# Mouse_Send_SCH.net
KiCad netlist of a schematic drawn in Altium Designer
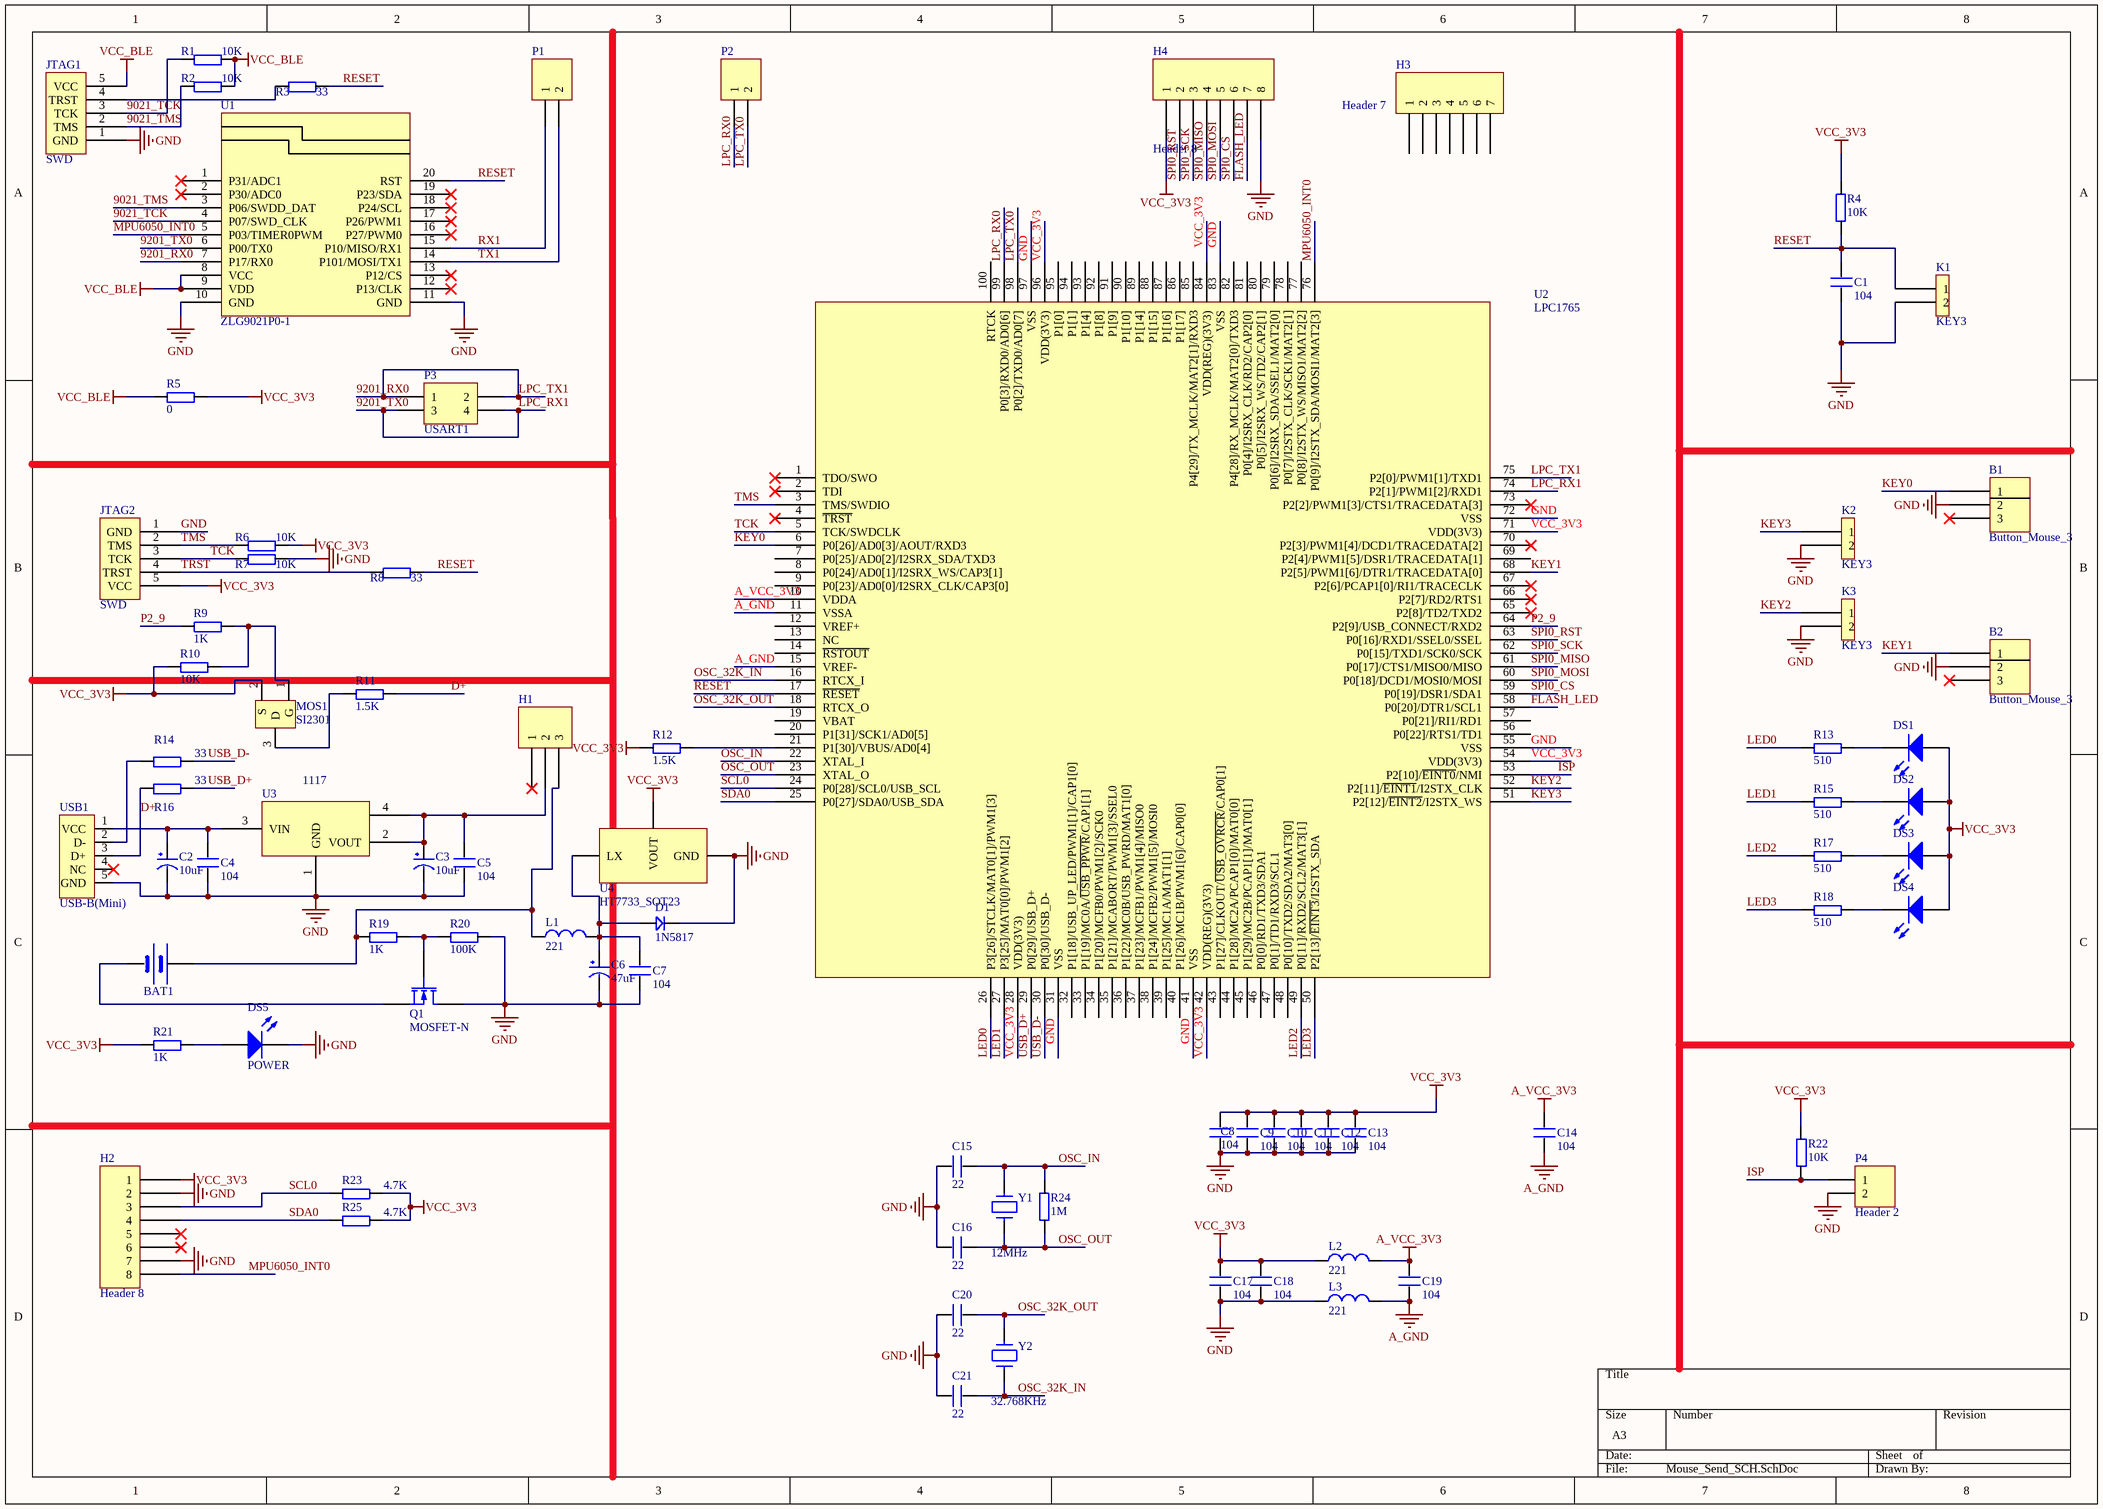
[diagram p0: Mouse_Send_SCH.SchDoc]

(export (version "E")
  (design (tool "Eeschema 10.0.6"))
  (components
    (comp (ref "B1")
      (value "Button_Mouse_3")
      (footprint "Button_Mouse_3")
      (libsource (lib "MY_SCH_Lib") (part "Button_Mouse_3"))
    )
    (comp (ref "B2")
      (value "Button_Mouse_3")
      (footprint "Button_Mouse_3")
      (libsource (lib "MY_SCH_Lib") (part "Button_Mouse_3"))
    )
    (comp (ref "BAT1") (value "BATT") (footprint "BAT_NUM5_2") (libsource (lib "MY_SCH_Lib") (part "BAT")))
    (comp (ref "C1") (value "104") (footprint "0603P") (libsource (lib "MY_SCH_Lib") (part "C")))
    (comp (ref "C2") (value "10uF") (footprint "TAJ_A") (libsource (lib "MY_SCH_Lib") (part "CAP")))
    (comp (ref "C3") (value "10uF") (footprint "TAJ_A") (libsource (lib "MY_SCH_Lib") (part "CAP")))
    (comp (ref "C4") (value "104") (footprint "0603P") (libsource (lib "MY_SCH_Lib") (part "C")))
    (comp (ref "C5") (value "104") (footprint "0603P") (libsource (lib "MY_SCH_Lib") (part "C")))
    (comp (ref "C6") (value "47uF") (footprint "TAJ_A") (libsource (lib "MY_SCH_Lib") (part "CAP")))
    (comp (ref "C7") (value "104") (footprint "0603P") (libsource (lib "MY_SCH_Lib") (part "C")))
    (comp (ref "C8") (value "104") (footprint "0603P") (libsource (lib "MY_SCH_Lib") (part "C")))
    (comp (ref "C9") (value "104") (footprint "0603P") (libsource (lib "MY_SCH_Lib") (part "C")))
    (comp (ref "C10") (value "104") (footprint "0603P") (libsource (lib "MY_SCH_Lib") (part "C")))
    (comp (ref "C11") (value "104") (footprint "0603P") (libsource (lib "MY_SCH_Lib") (part "C")))
    (comp (ref "C12") (value "104") (footprint "0603P") (libsource (lib "MY_SCH_Lib") (part "C")))
    (comp (ref "C13") (value "104") (footprint "0603P") (libsource (lib "MY_SCH_Lib") (part "C")))
    (comp (ref "C14") (value "104") (footprint "0603P") (libsource (lib "MY_SCH_Lib") (part "C")))
    (comp (ref "C15") (value "22") (footprint "0603P") (libsource (lib "MY_SCH_Lib") (part "C")))
    (comp (ref "C16") (value "22") (footprint "0603P") (libsource (lib "MY_SCH_Lib") (part "C")))
    (comp (ref "C17") (value "104") (footprint "0603P") (libsource (lib "MY_SCH_Lib") (part "C")))
    (comp (ref "C18") (value "104") (footprint "0603P") (libsource (lib "MY_SCH_Lib") (part "C")))
    (comp (ref "C19") (value "104") (footprint "0603P") (libsource (lib "MY_SCH_Lib") (part "C")))
    (comp (ref "C20") (value "22") (footprint "0603P") (libsource (lib "MY_SCH_Lib") (part "C")))
    (comp (ref "C21") (value "22") (footprint "0603P") (libsource (lib "MY_SCH_Lib") (part "C")))
    (comp (ref "D1") (value "1N5817") (footprint "DIODE_SOP") (libsource (lib "MY_SCH_Lib") (part "D")))
    (comp (ref "DS1")
      (value "~")
      (footprint "SMDLED")
      (description "Typical RED, GREEN, YELLOW, AMBER GaAs LED")
      (fields (field (name "PUBLISHER") "Altium Limited"))
      (libsource (lib "MY_SCH_Lib") (part "LED2"))
    )
    (comp (ref "DS2")
      (value "~")
      (footprint "SMDLED")
      (description "Typical RED, GREEN, YELLOW, AMBER GaAs LED")
      (fields (field (name "PUBLISHER") "Altium Limited"))
      (libsource (lib "MY_SCH_Lib") (part "LED2"))
    )
    (comp (ref "DS3")
      (value "~")
      (footprint "SMDLED")
      (description "Typical RED, GREEN, YELLOW, AMBER GaAs LED")
      (fields (field (name "PUBLISHER") "Altium Limited"))
      (libsource (lib "MY_SCH_Lib") (part "LED2"))
    )
    (comp (ref "DS4")
      (value "~")
      (footprint "SMDLED")
      (description "Typical RED, GREEN, YELLOW, AMBER GaAs LED")
      (fields (field (name "PUBLISHER") "Altium Limited"))
      (libsource (lib "MY_SCH_Lib") (part "LED2"))
    )
    (comp (ref "DS5")
      (value "POWER")
      (footprint "SMDLED")
      (description "Typical RED, GREEN, YELLOW, AMBER GaAs LED")
      (fields (field (name "PUBLISHER") "Altium Limited"))
      (libsource (lib "MY_SCH_Lib") (part "LED2"))
    )
    (comp (ref "H1") (value "~") (footprint "KEY_B") (libsource (lib "MY_SCH_Lib") (part "Header 3")))
    (comp (ref "H2")
      (value "Header 8")
      (footprint "Header 8")
      (libsource (lib "MY_SCH_Lib") (part "Header 8"))
    )
    (comp (ref "H3") (value "Header 7") (footprint "Head7") (libsource (lib "MY_SCH_Lib") (part "Header 7")))
    (comp (ref "H4") (value "Header 8") (footprint "Header 8") (libsource (lib "") (part "Header 8_1")))
    (comp (ref "JTAG1") (value "SWD") (footprint "HEAD5") (libsource (lib "") (part "SWD_1")))
    (comp (ref "JTAG2") (value "SWD") (footprint "HEAD5") (libsource (lib "MY_SCH_Lib") (part "SWD")))
    (comp (ref "K1") (value "KEY3") (footprint "KEY2") (libsource (lib "MY_SCH_Lib") (part "KEY3")))
    (comp (ref "K2") (value "KEY3") (footprint "KEY2") (libsource (lib "MY_SCH_Lib") (part "KEY3")))
    (comp (ref "K3") (value "KEY3") (footprint "KEY2") (libsource (lib "MY_SCH_Lib") (part "KEY3")))
    (comp (ref "L1") (value "221") (footprint "0603P") (libsource (lib "MY_SCH_Lib") (part "Inductor")))
    (comp (ref "L2") (value "221") (footprint "0603P") (libsource (lib "MY_SCH_Lib") (part "Inductor")))
    (comp (ref "L3") (value "221") (footprint "0603P") (libsource (lib "MY_SCH_Lib") (part "Inductor")))
    (comp (ref "MOS1")
      (value "SI2301")
      (footprint "SOT-23")
      (description "IRLML6401/SI2301")
      (libsource (lib "MY_SCH_Lib") (part "MOS-P"))
    )
    (comp (ref "P1")
      (value "~")
      (footprint "HDR1X2")
      (fields (field (name "PUBLISHER") "Altium Limited"))
      (libsource (lib "") (part "Header 2_1"))
    )
    (comp (ref "P2")
      (value "~")
      (footprint "HDR1X2")
      (fields (field (name "PUBLISHER") "Altium Limited"))
      (libsource (lib "") (part "Header 2_1"))
    )
    (comp (ref "P3")
      (value "USART1")
      (footprint "HDR2X2")
      (description "Header, 2-Pin, Dual row")
      (fields (field (name "PUBLISHER") "Altium Limited"))
      (libsource (lib "MY_SCH_Lib") (part "Header 2X2"))
    )
    (comp (ref "P4")
      (value "Header 2")
      (footprint "HDR1X2")
      (fields (field (name "PUBLISHER") "Altium Limited"))
      (libsource (lib "MY_SCH_Lib") (part "Header 2"))
    )
    (comp (ref "Q1")
      (value "MOSFET-N")
      (footprint "MOSFET_SOT23")
      (description "N-Channel MOSFET")
      (fields (field (name "PUBLISHER") "Altium Limited"))
      (libsource (lib "Miscellaneous Devices") (part "MOSFET-N"))
    )
    (comp (ref "R1") (value "10K") (footprint "0603P") (libsource (lib "MY_SCH_Lib") (part "R")))
    (comp (ref "R2") (value "10K") (footprint "0603P") (libsource (lib "MY_SCH_Lib") (part "R")))
    (comp (ref "R3") (value "33") (footprint "0603P") (libsource (lib "MY_SCH_Lib") (part "R")))
    (comp (ref "R4") (value "10K") (footprint "0603P") (libsource (lib "MY_SCH_Lib") (part "R")))
    (comp (ref "R5") (value "0") (footprint "0603P") (libsource (lib "MY_SCH_Lib") (part "R")))
    (comp (ref "R6") (value "10K") (footprint "0603P") (libsource (lib "MY_SCH_Lib") (part "R")))
    (comp (ref "R7") (value "10K") (footprint "0603P") (libsource (lib "MY_SCH_Lib") (part "R")))
    (comp (ref "R8") (value "33") (footprint "0603P") (libsource (lib "MY_SCH_Lib") (part "R")))
    (comp (ref "R9") (value "1K") (footprint "0603P") (libsource (lib "MY_SCH_Lib") (part "R")))
    (comp (ref "R10") (value "10K") (footprint "0603P") (libsource (lib "MY_SCH_Lib") (part "R")))
    (comp (ref "R11") (value "1.5K") (footprint "0603P") (libsource (lib "MY_SCH_Lib") (part "R")))
    (comp (ref "R12") (value "1.5K") (footprint "0603P") (libsource (lib "MY_SCH_Lib") (part "R")))
    (comp (ref "R13") (value "510") (footprint "0603P") (libsource (lib "MY_SCH_Lib") (part "R")))
    (comp (ref "R14") (value "33") (footprint "0603P") (libsource (lib "MY_SCH_Lib") (part "R")))
    (comp (ref "R15") (value "510") (footprint "0603P") (libsource (lib "MY_SCH_Lib") (part "R")))
    (comp (ref "R16") (value "33") (footprint "0603P") (libsource (lib "MY_SCH_Lib") (part "R")))
    (comp (ref "R17") (value "510") (footprint "0603P") (libsource (lib "MY_SCH_Lib") (part "R")))
    (comp (ref "R18") (value "510") (footprint "0603P") (libsource (lib "MY_SCH_Lib") (part "R")))
    (comp (ref "R19") (value "1K") (footprint "0603P") (libsource (lib "MY_SCH_Lib") (part "R")))
    (comp (ref "R20") (value "100K") (footprint "0603P") (libsource (lib "MY_SCH_Lib") (part "R")))
    (comp (ref "R21") (value "1K") (footprint "0603P") (libsource (lib "MY_SCH_Lib") (part "R")))
    (comp (ref "R22") (value "10K") (footprint "0603P") (libsource (lib "MY_SCH_Lib") (part "R")))
    (comp (ref "R23") (value "4.7K") (footprint "0603P") (libsource (lib "MY_SCH_Lib") (part "R")))
    (comp (ref "R24") (value "1M") (footprint "0603P") (libsource (lib "MY_SCH_Lib") (part "R")))
    (comp (ref "R25") (value "4.7K") (footprint "0603P") (libsource (lib "MY_SCH_Lib") (part "R")))
    (comp (ref "U1")
      (value "ZLG9021P0-1")
      (footprint "ZLG9021P0-1")
      (libsource (lib "MY_SCH_Lib") (part "ZLG9021P0-1"))
    )
    (comp (ref "U2")
      (value "LPC1765")
      (footprint "TQFP-100")
      (libsource (lib "LPC17xx_System_Sch_AD") (part "LPC1765"))
    )
    (comp (ref "U3") (value "1117") (footprint "AMS1117") (libsource (lib "MY_SCH_Lib") (part "1117")))
    (comp (ref "U4")
      (value "HT7733_SOT23")
      (footprint "SOT-23")
      (libsource (lib "LPC17xx_System_Sch_AD") (part "HT7733_SOT23"))
    )
    (comp (ref "USB1")
      (value "USB-B(Mini)")
      (footprint "USB/SM0.8-6H5")
      (libsource (lib "MY_SCH_Lib") (part "USB5"))
    )
    (comp (ref "Y1")
      (value "12MHz")
      (footprint "XTAL_US")
      (description "Crystal")
      (libsource (lib "LPC17xx_System_Sch_AD") (part "CRYSTAL"))
    )
    (comp (ref "Y2")
      (value "32.768KHz")
      (footprint "CRY-32")
      (description "Crystal")
      (libsource (lib "LPC17xx_System_Sch_AD") (part "CRYSTAL"))
    )
  )
  (nets
    (net (code "1") (name "/9021_TCK") (class "Default")
      (node (ref "JTAG1") (pin "3") (pinfunction "TCK_3") (pintype "passive"))
      (node (ref "R1") (pin "1") (pintype "passive"))
      (node (ref "U1") (pin "4") (pinfunction "P07/SWD_CLK_4") (pintype "passive"))
    )
    (net (code "2") (name "/9021_TMS") (class "Default")
      (node (ref "JTAG1") (pin "2") (pinfunction "TMS_2") (pintype "passive"))
      (node (ref "R2") (pin "1") (pintype "passive"))
      (node (ref "U1") (pin "3") (pinfunction "P06/SWDD_DAT_3") (pintype "passive"))
    )
    (net (code "3") (name "/9201_RX0") (class "Default")
      (node (ref "P3") (pin "1") (pinfunction "1_1") (pintype "passive"))
      (node (ref "P3") (pin "2") (pinfunction "2_2") (pintype "passive"))
      (node (ref "U1") (pin "7") (pinfunction "P17/RX0_7") (pintype "passive"))
      (node (ref "U2") (pin "75") (pinfunction "P2[0]/PWM1[1]/TXD1_75") (pintype "passive"))
    )
    (net (code "4") (name "/9201_TX0") (class "Default")
      (node (ref "P3") (pin "3") (pinfunction "3_3") (pintype "passive"))
      (node (ref "P3") (pin "4") (pinfunction "4_4") (pintype "passive"))
      (node (ref "U1") (pin "6") (pinfunction "P00/TX0_6") (pintype "passive"))
      (node (ref "U2") (pin "74") (pinfunction "P2[1]/PWM1[2]/RXD1_74") (pintype "passive"))
    )
    (net (code "5") (name "/D+") (class "Default")
      (node (ref "R11") (pin "2") (pintype "passive"))
      (node (ref "R16") (pin "1") (pintype "passive"))
      (node (ref "USB1") (pin "3") (pinfunction "D+_3") (pintype "passive"))
    )
    (net (code "6") (name "/FLASH_LED") (class "Default")
      (node (ref "H4") (pin "7") (pinfunction "7_7") (pintype "passive"))
      (node (ref "U2") (pin "58") (pinfunction "P0[20]/DTR1/SCL1_58") (pintype "passive"))
    )
    (net (code "7") (name "/ISP") (class "Default")
      (node (ref "P4") (pin "1") (pinfunction "1_1") (pintype "passive"))
      (node (ref "R22") (pin "1") (pintype "passive"))
      (node (ref "U2") (pin "53") (pinfunction "P2[10]/~{EINT0}/NMI_53") (pintype "passive"))
    )
    (net (code "8") (name "/KEY0") (class "Default")
      (node (ref "B1") (pin "1") (pinfunction "1_1") (pintype "passive"))
      (node (ref "U2") (pin "6") (pinfunction "P0[26]/AD0[3]/AOUT/RXD3_6") (pintype "passive"))
    )
    (net (code "9") (name "/KEY1") (class "Default")
      (node (ref "B2") (pin "1") (pinfunction "1_1") (pintype "passive"))
      (node (ref "U2") (pin "68") (pinfunction "P2[5]/PWM1[6]/DTR1/TRACEDATA[0]_68") (pintype "passive"))
    )
    (net (code "10") (name "/KEY2") (class "Default")
      (node (ref "K3") (pin "1") (pinfunction "1_1") (pintype "passive"))
      (node (ref "U2") (pin "52") (pinfunction "P2[11]/~{EINT1}/I2STX_CLK_52") (pintype "passive"))
    )
    (net (code "11") (name "/KEY3") (class "Default")
      (node (ref "K2") (pin "1") (pinfunction "1_1") (pintype "passive"))
      (node (ref "U2") (pin "51") (pinfunction "P2[12]/~{EINT2}/I2STX_WS_51") (pintype "passive"))
    )
    (net (code "12") (name "/LED0") (class "Default")
      (node (ref "R13") (pin "1") (pintype "passive"))
      (node (ref "U2") (pin "26") (pinfunction "P3[26]/STCLK/MAT0[1]/PWM1[3]_26") (pintype "passive"))
    )
    (net (code "13") (name "/LED1") (class "Default")
      (node (ref "R15") (pin "1") (pintype "passive"))
      (node (ref "U2") (pin "27") (pinfunction "P3[25]/MAT0[0]/PWM1[2]_27") (pintype "passive"))
    )
    (net (code "14") (name "/LED2") (class "Default")
      (node (ref "R17") (pin "1") (pintype "passive"))
      (node (ref "U2") (pin "49") (pinfunction "P0[11]/RXD2/SCL2/MAT3[1]_49") (pintype "passive"))
    )
    (net (code "15") (name "/LED3") (class "Default")
      (node (ref "R18") (pin "1") (pintype "passive"))
      (node (ref "U2") (pin "50") (pinfunction "P2[13]/~{EINT3}/I2STX_SDA_50") (pintype "passive"))
    )
    (net (code "16") (name "/LPC_RX0") (class "Default")
      (node (ref "P2") (pin "1") (pinfunction "1_1") (pintype "passive"))
      (node (ref "U2") (pin "99") (pinfunction "P0[3]/RXD0/AD0[6]_99") (pintype "passive"))
    )
    (net (code "17") (name "/LPC_TX0") (class "Default")
      (node (ref "P2") (pin "2") (pinfunction "2_2") (pintype "passive"))
      (node (ref "U2") (pin "98") (pinfunction "P0[2]/TXD0/AD0[7]_98") (pintype "passive"))
    )
    (net (code "18") (name "/MPU6050_INT0") (class "Default")
      (node (ref "H2") (pin "8") (pinfunction "8_8") (pintype "passive"))
      (node (ref "U1") (pin "5") (pinfunction "P03/TIMER0PWM_5") (pintype "passive"))
      (node (ref "U2") (pin "76") (pinfunction "P0[9]/I2STX_SDA/MOSI1/MAT2[3]_76") (pintype "passive"))
    )
    (net (code "19") (name "/OSC_32K_IN") (class "Default")
      (node (ref "C21") (pin "2") (pintype "passive"))
      (node (ref "U2") (pin "16") (pinfunction "RTCX_I_16") (pintype "passive"))
      (node (ref "Y2") (pin "1") (pinfunction "1_1") (pintype "passive"))
    )
    (net (code "20") (name "/OSC_32K_OUT") (class "Default")
      (node (ref "C20") (pin "2") (pintype "passive"))
      (node (ref "U2") (pin "18") (pinfunction "RTCX_O_18") (pintype "passive"))
      (node (ref "Y2") (pin "2") (pinfunction "2_2") (pintype "passive"))
    )
    (net (code "21") (name "/OSC_IN") (class "Default")
      (node (ref "C15") (pin "2") (pintype "passive"))
      (node (ref "R24") (pin "1") (pintype "passive"))
      (node (ref "U2") (pin "22") (pinfunction "XTAL_I_22") (pintype "passive"))
      (node (ref "Y1") (pin "2") (pinfunction "2_2") (pintype "passive"))
    )
    (net (code "22") (name "/OSC_OUT") (class "Default")
      (node (ref "C16") (pin "2") (pintype "passive"))
      (node (ref "R24") (pin "2") (pintype "passive"))
      (node (ref "U2") (pin "23") (pinfunction "XTAL_O_23") (pintype "passive"))
      (node (ref "Y1") (pin "1") (pinfunction "1_1") (pintype "passive"))
    )
    (net (code "23") (name "/P2_9") (class "Default")
      (node (ref "R9") (pin "1") (pintype "passive"))
      (node (ref "U2") (pin "64") (pinfunction "P2[9]/USB_CONNECT/RXD2_64") (pintype "passive"))
    )
    (net (code "24") (name "/RESET") (class "Default")
      (node (ref "C1") (pin "2") (pintype "passive"))
      (node (ref "K1") (pin "1") (pinfunction "1_1") (pintype "passive"))
      (node (ref "R3") (pin "2") (pintype "passive"))
      (node (ref "R4") (pin "1") (pintype "passive"))
      (node (ref "R8") (pin "2") (pintype "passive"))
      (node (ref "U1") (pin "20") (pinfunction "RST_20") (pintype "passive"))
      (node (ref "U2") (pin "17") (pinfunction "~{RESET}_17") (pintype "passive"))
    )
    (net (code "25") (name "/RX1") (class "Default")
      (node (ref "P1") (pin "1") (pinfunction "1_1") (pintype "passive"))
      (node (ref "U1") (pin "15") (pinfunction "P10/MISO/RX1_15") (pintype "passive"))
    )
    (net (code "26") (name "/SCL0") (class "Default")
      (node (ref "H2") (pin "3") (pinfunction "3_3") (pintype "passive"))
      (node (ref "R23") (pin "1") (pintype "passive"))
      (node (ref "U2") (pin "24") (pinfunction "P0[28]/SCL0/USB_SCL_24") (pintype "passive"))
    )
    (net (code "27") (name "/SDA0") (class "Default")
      (node (ref "H2") (pin "4") (pinfunction "4_4") (pintype "passive"))
      (node (ref "R25") (pin "1") (pintype "passive"))
      (node (ref "U2") (pin "25") (pinfunction "P0[27]/SDA0/USB_SDA_25") (pintype "passive"))
    )
    (net (code "28") (name "/SPI0_CS") (class "Default")
      (node (ref "H4") (pin "6") (pinfunction "6_6") (pintype "passive"))
      (node (ref "U2") (pin "59") (pinfunction "P0[19]/DSR1/SDA1_59") (pintype "passive"))
    )
    (net (code "29") (name "/SPI0_MISO") (class "Default")
      (node (ref "H4") (pin "4") (pinfunction "4_4") (pintype "passive"))
      (node (ref "U2") (pin "61") (pinfunction "P0[17]/CTS1/MISO0/MISO_61") (pintype "passive"))
    )
    (net (code "30") (name "/SPI0_MOSI") (class "Default")
      (node (ref "H4") (pin "5") (pinfunction "5_5") (pintype "passive"))
      (node (ref "U2") (pin "60") (pinfunction "P0[18]/DCD1/MOSI0/MOSI_60") (pintype "passive"))
    )
    (net (code "31") (name "/SPI0_RST") (class "Default")
      (node (ref "H4") (pin "2") (pinfunction "2_2") (pintype "passive"))
      (node (ref "U2") (pin "63") (pinfunction "P0[16]/RXD1/SSEL0/SSEL_63") (pintype "passive"))
    )
    (net (code "32") (name "/SPI0_SCK") (class "Default")
      (node (ref "H4") (pin "3") (pinfunction "3_3") (pintype "passive"))
      (node (ref "U2") (pin "62") (pinfunction "P0[15]/TXD1/SCK0/SCK_62") (pintype "passive"))
    )
    (net (code "33") (name "/TCK") (class "Default")
      (node (ref "JTAG2") (pin "3") (pinfunction "TCK_3") (pintype "passive"))
      (node (ref "R7") (pin "1") (pintype "passive"))
      (node (ref "U2") (pin "5") (pinfunction "TCK/SWDCLK_5") (pintype "passive"))
    )
    (net (code "34") (name "/TMS") (class "Default")
      (node (ref "JTAG2") (pin "2") (pinfunction "TMS_2") (pintype "passive"))
      (node (ref "R6") (pin "1") (pintype "passive"))
      (node (ref "U2") (pin "3") (pinfunction "TMS/SWDIO_3") (pintype "passive"))
    )
    (net (code "35") (name "/TRST") (class "Default")
      (node (ref "JTAG2") (pin "4") (pinfunction "TRST_4") (pintype "passive"))
      (node (ref "R8") (pin "1") (pintype "passive"))
    )
    (net (code "36") (name "/TX1") (class "Default")
      (node (ref "P1") (pin "2") (pinfunction "2_2") (pintype "passive"))
      (node (ref "U1") (pin "14") (pinfunction "P101/MOSI/TX1_14") (pintype "passive"))
    )
    (net (code "37") (name "/USB_D+") (class "Default")
      (node (ref "R16") (pin "2") (pintype "passive"))
      (node (ref "U2") (pin "29") (pinfunction "P0[29]/USB_D+_29") (pintype "passive"))
    )
    (net (code "38") (name "/USB_D-") (class "Default")
      (node (ref "R14") (pin "2") (pintype "passive"))
      (node (ref "U2") (pin "30") (pinfunction "P0[30]/USB_D-_30") (pintype "passive"))
    )
    (net (code "39") (name "A_GND") (class "Default")
      (node (ref "C14") (pin "2") (pintype "passive"))
      (node (ref "C19") (pin "1") (pintype "passive"))
      (node (ref "L3") (pin "2") (pinfunction "2_2") (pintype "passive"))
      (node (ref "U2") (pin "11") (pinfunction "VSSA_11") (pintype "passive"))
      (node (ref "U2") (pin "15") (pinfunction "VREF-_15") (pintype "passive"))
    )
    (net (code "40") (name "A_VCC_3V3") (class "Default")
      (node (ref "C14") (pin "1") (pintype "passive"))
      (node (ref "C19") (pin "2") (pintype "passive"))
      (node (ref "L2") (pin "2") (pinfunction "2_2") (pintype "passive"))
      (node (ref "U2") (pin "10") (pinfunction "VDDA_10") (pintype "passive"))
    )
    (net (code "41") (name "GND") (class "Default")
      (node (ref "B1") (pin "2") (pinfunction "2_2") (pintype "passive"))
      (node (ref "B2") (pin "2") (pinfunction "2_2") (pintype "passive"))
      (node (ref "C1") (pin "1") (pintype "passive"))
      (node (ref "C10") (pin "2") (pintype "passive"))
      (node (ref "C11") (pin "2") (pintype "passive"))
      (node (ref "C12") (pin "2") (pintype "passive"))
      (node (ref "C13") (pin "2") (pintype "passive"))
      (node (ref "C15") (pin "1") (pintype "passive"))
      (node (ref "C16") (pin "1") (pintype "passive"))
      (node (ref "C17") (pin "1") (pintype "passive"))
      (node (ref "C18") (pin "1") (pintype "passive"))
      (node (ref "C2") (pin "2") (pinfunction "GND_2") (pintype "passive"))
      (node (ref "C20") (pin "1") (pintype "passive"))
      (node (ref "C21") (pin "1") (pintype "passive"))
      (node (ref "C3") (pin "2") (pinfunction "GND_2") (pintype "passive"))
      (node (ref "C4") (pin "1") (pintype "passive"))
      (node (ref "C5") (pin "1") (pintype "passive"))
      (node (ref "C6") (pin "2") (pinfunction "GND_2") (pintype "passive"))
      (node (ref "C7") (pin "1") (pintype "passive"))
      (node (ref "C8") (pin "2") (pintype "passive"))
      (node (ref "C9") (pin "2") (pintype "passive"))
      (node (ref "D1") (pin "2") (pintype "passive"))
      (node (ref "DS5") (pin "2") (pinfunction "K_2") (pintype "passive"))
      (node (ref "H2") (pin "2") (pinfunction "2_2") (pintype "passive"))
      (node (ref "H2") (pin "7") (pinfunction "7_7") (pintype "passive"))
      (node (ref "H4") (pin "8") (pinfunction "8_8") (pintype "passive"))
      (node (ref "JTAG1") (pin "1") (pinfunction "GND_1") (pintype "passive"))
      (node (ref "JTAG2") (pin "1") (pinfunction "GND_1") (pintype "passive"))
      (node (ref "K1") (pin "2") (pinfunction "2_2") (pintype "passive"))
      (node (ref "K2") (pin "2") (pinfunction "2_2") (pintype "passive"))
      (node (ref "K3") (pin "2") (pinfunction "2_2") (pintype "passive"))
      (node (ref "L3") (pin "1") (pinfunction "1_1") (pintype "passive"))
      (node (ref "P4") (pin "2") (pinfunction "2_2") (pintype "passive"))
      (node (ref "Q1") (pin "1") (pinfunction "D_1") (pintype "passive"))
      (node (ref "R20") (pin "2") (pintype "passive"))
      (node (ref "R7") (pin "2") (pintype "passive"))
      (node (ref "U1") (pin "10") (pinfunction "GND_10") (pintype "passive"))
      (node (ref "U1") (pin "11") (pinfunction "GND_11") (pintype "passive"))
      (node (ref "U2") (pin "31") (pinfunction "VSS_31") (pintype "passive"))
      (node (ref "U2") (pin "41") (pinfunction "VSS_41") (pintype "passive"))
      (node (ref "U2") (pin "55") (pinfunction "VSS_55") (pintype "passive"))
      (node (ref "U2") (pin "72") (pinfunction "VSS_72") (pintype "passive"))
      (node (ref "U2") (pin "83") (pinfunction "VSS_83") (pintype "passive"))
      (node (ref "U2") (pin "97") (pinfunction "VSS_97") (pintype "passive"))
      (node (ref "U3") (pin "1") (pinfunction "GND_1") (pintype "passive"))
      (node (ref "U4") (pin "1") (pinfunction "GND_1") (pintype "passive"))
      (node (ref "USB1") (pin "5") (pinfunction "GND_5") (pintype "passive"))
    )
    (net (code "42") (name "Net-(BAT1-GND)") (class "Default")
      (node (ref "BAT1") (pin "2") (pinfunction "GND_2") (pintype "passive"))
      (node (ref "Q1") (pin "3") (pinfunction "S_3") (pintype "passive"))
    )
    (net (code "43") (name "Net-(BAT1-VCC)") (class "Default")
      (node (ref "BAT1") (pin "1") (pinfunction "VCC_1") (pintype "passive"))
      (node (ref "H1") (pin "3") (pinfunction "3_3") (pintype "passive"))
      (node (ref "L1") (pin "1") (pinfunction "1_1") (pintype "passive"))
      (node (ref "R19") (pin "1") (pintype "passive"))
    )
    (net (code "44") (name "Net-(C2-VCC)") (class "Default")
      (node (ref "C2") (pin "1") (pinfunction "VCC_1") (pintype "passive"))
      (node (ref "C4") (pin "2") (pintype "passive"))
      (node (ref "U3") (pin "3") (pinfunction "VIN_3") (pintype "passive"))
      (node (ref "USB1") (pin "1") (pinfunction "VCC_1") (pintype "passive"))
    )
    (net (code "45") (name "Net-(C3-VCC)") (class "Default")
      (node (ref "C3") (pin "1") (pinfunction "VCC_1") (pintype "passive"))
      (node (ref "C5") (pin "2") (pintype "passive"))
      (node (ref "H1") (pin "2") (pinfunction "2_2") (pintype "passive"))
      (node (ref "U3") (pin "2") (pinfunction "VOUT_2") (pintype "passive"))
      (node (ref "U3") (pin "4") (pinfunction "4_4") (pintype "passive"))
    )
    (net (code "46") (name "Net-(C6-VCC)") (class "Default")
      (node (ref "C6") (pin "1") (pinfunction "VCC_1") (pintype "passive"))
      (node (ref "C7") (pin "2") (pintype "passive"))
      (node (ref "D1") (pin "1") (pintype "passive"))
      (node (ref "L1") (pin "2") (pinfunction "2_2") (pintype "passive"))
      (node (ref "U4") (pin "2") (pinfunction "LX_2") (pintype "passive"))
    )
    (net (code "47") (name "Net-(DS1-K)") (class "Default")
      (node (ref "DS1") (pin "2") (pinfunction "K_2") (pintype "passive"))
      (node (ref "R13") (pin "2") (pintype "passive"))
    )
    (net (code "48") (name "Net-(DS2-K)") (class "Default")
      (node (ref "DS2") (pin "2") (pinfunction "K_2") (pintype "passive"))
      (node (ref "R15") (pin "2") (pintype "passive"))
    )
    (net (code "49") (name "Net-(DS3-K)") (class "Default")
      (node (ref "DS3") (pin "2") (pinfunction "K_2") (pintype "passive"))
      (node (ref "R17") (pin "2") (pintype "passive"))
    )
    (net (code "50") (name "Net-(DS4-K)") (class "Default")
      (node (ref "DS4") (pin "2") (pinfunction "K_2") (pintype "passive"))
      (node (ref "R18") (pin "2") (pintype "passive"))
    )
    (net (code "51") (name "Net-(DS5-A)") (class "Default")
      (node (ref "DS5") (pin "1") (pinfunction "A_1") (pintype "passive"))
      (node (ref "R21") (pin "2") (pintype "passive"))
    )
    (net (code "52") (name "Net-(JTAG1-TRST)") (class "Default")
      (node (ref "JTAG1") (pin "4") (pinfunction "TRST_4") (pintype "passive"))
      (node (ref "R3") (pin "1") (pintype "passive"))
    )
    (net (code "53") (name "Net-(MOS1-D)") (class "Default")
      (node (ref "MOS1") (pin "3") (pinfunction "D_3") (pintype "passive"))
      (node (ref "R11") (pin "1") (pintype "passive"))
    )
    (net (code "54") (name "Net-(MOS1-G)") (class "Default")
      (node (ref "MOS1") (pin "1") (pinfunction "G_1") (pintype "passive"))
      (node (ref "R10") (pin "2") (pintype "passive"))
      (node (ref "R9") (pin "2") (pintype "passive"))
    )
    (net (code "55") (name "Net-(Q1-G)") (class "Default")
      (node (ref "Q1") (pin "2") (pinfunction "G_2") (pintype "passive"))
      (node (ref "R19") (pin "2") (pintype "passive"))
      (node (ref "R20") (pin "1") (pintype "passive"))
    )
    (net (code "56") (name "Net-(U2-P1[30]{slash}VBUS{slash}AD0[4])") (class "Default")
      (node (ref "R12") (pin "2") (pintype "passive"))
      (node (ref "U2") (pin "21") (pinfunction "P1[30]/VBUS/AD0[4]_21") (pintype "passive"))
    )
    (net (code "57") (name "Net-(USB1-D-)") (class "Default")
      (node (ref "R14") (pin "1") (pintype "passive"))
      (node (ref "USB1") (pin "2") (pinfunction "D-_2") (pintype "passive"))
    )
    (net (code "58") (name "VCC_3V3") (class "Default")
      (node (ref "C10") (pin "1") (pintype "passive"))
      (node (ref "C11") (pin "1") (pintype "passive"))
      (node (ref "C12") (pin "1") (pintype "passive"))
      (node (ref "C13") (pin "1") (pintype "passive"))
      (node (ref "C17") (pin "2") (pintype "passive"))
      (node (ref "C18") (pin "2") (pintype "passive"))
      (node (ref "C8") (pin "1") (pintype "passive"))
      (node (ref "C9") (pin "1") (pintype "passive"))
      (node (ref "DS1") (pin "1") (pinfunction "A_1") (pintype "passive"))
      (node (ref "DS2") (pin "1") (pinfunction "A_1") (pintype "passive"))
      (node (ref "DS3") (pin "1") (pinfunction "A_1") (pintype "passive"))
      (node (ref "DS4") (pin "1") (pinfunction "A_1") (pintype "passive"))
      (node (ref "H2") (pin "1") (pinfunction "1_1") (pintype "passive"))
      (node (ref "H4") (pin "1") (pinfunction "1_1") (pintype "passive"))
      (node (ref "JTAG2") (pin "5") (pinfunction "VCC_5") (pintype "passive"))
      (node (ref "L2") (pin "1") (pinfunction "1_1") (pintype "passive"))
      (node (ref "MOS1") (pin "2") (pinfunction "S_2") (pintype "passive"))
      (node (ref "R10") (pin "1") (pintype "passive"))
      (node (ref "R12") (pin "1") (pintype "passive"))
      (node (ref "R21") (pin "1") (pintype "passive"))
      (node (ref "R22") (pin "2") (pintype "passive"))
      (node (ref "R23") (pin "2") (pintype "passive"))
      (node (ref "R25") (pin "2") (pintype "passive"))
      (node (ref "R4") (pin "2") (pintype "passive"))
      (node (ref "R5") (pin "2") (pintype "passive"))
      (node (ref "R6") (pin "2") (pintype "passive"))
      (node (ref "U2") (pin "28") (pinfunction "VDD(3V3)_28") (pintype "passive"))
      (node (ref "U2") (pin "42") (pinfunction "VDD(REG)(3V3)_42") (pintype "passive"))
      (node (ref "U2") (pin "54") (pinfunction "VDD(3V3)_54") (pintype "passive"))
      (node (ref "U2") (pin "71") (pinfunction "VDD(3V3)_71") (pintype "passive"))
      (node (ref "U2") (pin "84") (pinfunction "VDD(REG)(3V3)_84") (pintype "passive"))
      (node (ref "U2") (pin "96") (pinfunction "VDD(3V3)_96") (pintype "passive"))
      (node (ref "U4") (pin "3") (pinfunction "VOUT_3") (pintype "passive"))
    )
    (net (code "59") (name "VCC_BLE") (class "Default")
      (node (ref "JTAG1") (pin "5") (pinfunction "VCC_5") (pintype "passive"))
      (node (ref "R1") (pin "2") (pintype "passive"))
      (node (ref "R2") (pin "2") (pintype "passive"))
      (node (ref "R5") (pin "1") (pintype "passive"))
      (node (ref "U1") (pin "8") (pinfunction "VCC_8") (pintype "passive"))
      (node (ref "U1") (pin "9") (pinfunction "VDD_9") (pintype "passive"))
    )
    (net (code "60") (name "unconnected-(B1-Pad3)") (class "Default")
      (node (ref "B1") (pin "3") (pinfunction "3_3") (pintype "passive+no_connect"))
    )
    (net (code "61") (name "unconnected-(B2-Pad3)") (class "Default")
      (node (ref "B2") (pin "3") (pinfunction "3_3") (pintype "passive+no_connect"))
    )
    (net (code "62") (name "unconnected-(H1-Pad1)") (class "Default")
      (node (ref "H1") (pin "1") (pinfunction "1_1") (pintype "passive+no_connect"))
    )
    (net (code "63") (name "unconnected-(H2-Pad5)") (class "Default")
      (node (ref "H2") (pin "5") (pinfunction "5_5") (pintype "passive+no_connect"))
    )
    (net (code "64") (name "unconnected-(H2-Pad6)") (class "Default")
      (node (ref "H2") (pin "6") (pinfunction "6_6") (pintype "passive+no_connect"))
    )
    (net (code "65") (name "unconnected-(H3-Pad1)") (class "Default")
      (node (ref "H3") (pin "1") (pinfunction "1_1") (pintype "passive"))
    )
    (net (code "66") (name "unconnected-(H3-Pad2)") (class "Default")
      (node (ref "H3") (pin "2") (pinfunction "2_2") (pintype "passive"))
    )
    (net (code "67") (name "unconnected-(H3-Pad3)") (class "Default")
      (node (ref "H3") (pin "3") (pinfunction "3_3") (pintype "passive"))
    )
    (net (code "68") (name "unconnected-(H3-Pad4)") (class "Default")
      (node (ref "H3") (pin "4") (pinfunction "4_4") (pintype "passive"))
    )
    (net (code "69") (name "unconnected-(H3-Pad5)") (class "Default")
      (node (ref "H3") (pin "5") (pinfunction "5_5") (pintype "passive"))
    )
    (net (code "70") (name "unconnected-(H3-Pad6)") (class "Default")
      (node (ref "H3") (pin "6") (pinfunction "6_6") (pintype "passive"))
    )
    (net (code "71") (name "unconnected-(H3-Pad7)") (class "Default")
      (node (ref "H3") (pin "7") (pinfunction "7_7") (pintype "passive"))
    )
    (net (code "72") (name "unconnected-(U1-P12{slash}CS-Pad13)") (class "Default")
      (node (ref "U1") (pin "13") (pinfunction "P12/CS_13") (pintype "passive+no_connect"))
    )
    (net (code "73") (name "unconnected-(U1-P13{slash}CLK-Pad12)") (class "Default")
      (node (ref "U1") (pin "12") (pinfunction "P13/CLK_12") (pintype "passive+no_connect"))
    )
    (net (code "74") (name "unconnected-(U1-P23{slash}SDA-Pad19)") (class "Default")
      (node (ref "U1") (pin "19") (pinfunction "P23/SDA_19") (pintype "passive+no_connect"))
    )
    (net (code "75") (name "unconnected-(U1-P24{slash}SCL-Pad18)") (class "Default")
      (node (ref "U1") (pin "18") (pinfunction "P24/SCL_18") (pintype "passive+no_connect"))
    )
    (net (code "76") (name "unconnected-(U1-P26{slash}PWM1-Pad17)") (class "Default")
      (node (ref "U1") (pin "17") (pinfunction "P26/PWM1_17") (pintype "passive+no_connect"))
    )
    (net (code "77") (name "unconnected-(U1-P27{slash}PWM0-Pad16)") (class "Default")
      (node (ref "U1") (pin "16") (pinfunction "P27/PWM0_16") (pintype "passive+no_connect"))
    )
    (net (code "78") (name "unconnected-(U1-P30{slash}ADC0-Pad2)") (class "Default")
      (node (ref "U1") (pin "2") (pinfunction "P30/ADC0_2") (pintype "passive+no_connect"))
    )
    (net (code "79") (name "unconnected-(U1-P31{slash}ADC1-Pad1)") (class "Default")
      (node (ref "U1") (pin "1") (pinfunction "P31/ADC1_1") (pintype "passive+no_connect"))
    )
    (net (code "80") (name "unconnected-(U2-NC-Pad13)") (class "Default")
      (node (ref "U2") (pin "13") (pinfunction "NC_13") (pintype "passive"))
    )
    (net (code "81") (name "unconnected-(U2-P0[0]{slash}RD1{slash}TXD3{slash}SDA1-Pad46)") (class "Default")
      (node (ref "U2") (pin "46") (pinfunction "P0[0]/RD1/TXD3/SDA1_46") (pintype "passive"))
    )
    (net (code "82") (name "unconnected-(U2-P0[1]{slash}TD1{slash}RXD3{slash}SCL1-Pad47)") (class "Default")
      (node (ref "U2") (pin "47") (pinfunction "P0[1]/TD1/RXD3/SCL1_47") (pintype "passive"))
    )
    (net (code "83") (name "unconnected-(U2-P0[4]{slash}I2SRX_CLK{slash}RD2{slash}CAP2[0]-Pad81)") (class "Default")
      (node (ref "U2") (pin "81") (pinfunction "P0[4]/I2SRX_CLK/RD2/CAP2[0]_81") (pintype "passive"))
    )
    (net (code "84") (name "unconnected-(U2-P0[5]{slash}I2SRX_WS{slash}TD2{slash}CAP2[1]-Pad80)") (class "Default")
      (node (ref "U2") (pin "80") (pinfunction "P0[5]/I2SRX_WS/TD2/CAP2[1]_80") (pintype "passive"))
    )
    (net (code "85") (name "unconnected-(U2-P0[6]{slash}I2SRX_SDA{slash}SSEL1{slash}MAT2[0]-Pad79)") (class "Default")
      (node (ref "U2") (pin "79") (pinfunction "P0[6]/I2SRX_SDA/SSEL1/MAT2[0]_79") (pintype "passive"))
    )
    (net (code "86") (name "unconnected-(U2-P0[7]{slash}I2STX_CLK{slash}SCK1{slash}MAT2[1]-Pad78)") (class "Default")
      (node (ref "U2") (pin "78") (pinfunction "P0[7]/I2STX_CLK/SCK1/MAT2[1]_78") (pintype "passive"))
    )
    (net (code "87") (name "unconnected-(U2-P0[8]{slash}I2STX_WS{slash}MISO1{slash}MAT2[2]-Pad77)") (class "Default")
      (node (ref "U2") (pin "77") (pinfunction "P0[8]/I2STX_WS/MISO1/MAT2[2]_77") (pintype "passive"))
    )
    (net (code "88") (name "unconnected-(U2-P0[10]{slash}TXD2{slash}SDA2{slash}MAT3[0]-Pad48)") (class "Default")
      (node (ref "U2") (pin "48") (pinfunction "P0[10]/TXD2/SDA2/MAT3[0]_48") (pintype "passive"))
    )
    (net (code "89") (name "unconnected-(U2-P0[21]{slash}RI1{slash}RD1-Pad57)") (class "Default")
      (node (ref "U2") (pin "57") (pinfunction "P0[21]/RI1/RD1_57") (pintype "passive"))
    )
    (net (code "90") (name "unconnected-(U2-P0[22]{slash}RTS1{slash}TD1-Pad56)") (class "Default")
      (node (ref "U2") (pin "56") (pinfunction "P0[22]/RTS1/TD1_56") (pintype "passive"))
    )
    (net (code "91") (name "unconnected-(U2-P0[23]{slash}AD0[0]{slash}I2SRX_CLK{slash}CAP3[0]-Pad9)") (class "Default")
      (node (ref "U2") (pin "9") (pinfunction "P0[23]/AD0[0]/I2SRX_CLK/CAP3[0]_9") (pintype "passive"))
    )
    (net (code "92") (name "unconnected-(U2-P0[24]{slash}AD0[1]{slash}I2SRX_WS{slash}CAP3[1]-Pad8)") (class "Default")
      (node (ref "U2") (pin "8") (pinfunction "P0[24]/AD0[1]/I2SRX_WS/CAP3[1]_8") (pintype "passive"))
    )
    (net (code "93") (name "unconnected-(U2-P0[25]{slash}AD0[2]{slash}I2SRX_SDA{slash}TXD3-Pad7)") (class "Default")
      (node (ref "U2") (pin "7") (pinfunction "P0[25]/AD0[2]/I2SRX_SDA/TXD3_7") (pintype "passive"))
    )
    (net (code "94") (name "unconnected-(U2-P1[0]-Pad95)") (class "Default")
      (node (ref "U2") (pin "95") (pinfunction "P1[0]_95") (pintype "passive"))
    )
    (net (code "95") (name "unconnected-(U2-P1[1]-Pad94)") (class "Default")
      (node (ref "U2") (pin "94") (pinfunction "P1[1]_94") (pintype "passive"))
    )
    (net (code "96") (name "unconnected-(U2-P1[4]-Pad93)") (class "Default")
      (node (ref "U2") (pin "93") (pinfunction "P1[4]_93") (pintype "passive"))
    )
    (net (code "97") (name "unconnected-(U2-P1[8]-Pad92)") (class "Default")
      (node (ref "U2") (pin "92") (pinfunction "P1[8]_92") (pintype "passive"))
    )
    (net (code "98") (name "unconnected-(U2-P1[9]-Pad91)") (class "Default")
      (node (ref "U2") (pin "91") (pinfunction "P1[9]_91") (pintype "passive"))
    )
    (net (code "99") (name "unconnected-(U2-P1[10]-Pad90)") (class "Default")
      (node (ref "U2") (pin "90") (pinfunction "P1[10]_90") (pintype "passive"))
    )
    (net (code "100") (name "unconnected-(U2-P1[14]-Pad89)") (class "Default")
      (node (ref "U2") (pin "89") (pinfunction "P1[14]_89") (pintype "passive"))
    )
    (net (code "101") (name "unconnected-(U2-P1[15]-Pad88)") (class "Default")
      (node (ref "U2") (pin "88") (pinfunction "P1[15]_88") (pintype "passive"))
    )
    (net (code "102") (name "unconnected-(U2-P1[16]-Pad87)") (class "Default")
      (node (ref "U2") (pin "87") (pinfunction "P1[16]_87") (pintype "passive"))
    )
    (net (code "103") (name "unconnected-(U2-P1[17]-Pad86)") (class "Default")
      (node (ref "U2") (pin "86") (pinfunction "P1[17]_86") (pintype "passive"))
    )
    (net (code "104") (name "unconnected-(U2-P1[18]{slash}USB_UP_LED{slash}PWM1[1]{slash}CAP1[0]-Pad32)") (class "Default")
      (node (ref "U2") (pin "32") (pinfunction "P1[18]/USB_UP_LED/PWM1[1]/CAP1[0]_32") (pintype "passive"))
    )
    (net (code "105") (name "unconnected-(U2-P1[19]{slash}MC0A{slash}~{USB_PPWR}{slash}CAP1[1]-Pad33)") (class "Default")
      (node (ref "U2") (pin "33") (pinfunction "P1[19]/MC0A/~{USB_PPWR}/CAP1[1]_33") (pintype "passive"))
    )
    (net (code "106") (name "unconnected-(U2-P1[20]{slash}MCFB0{slash}PWM1[2]{slash}SCK0-Pad34)") (class "Default")
      (node (ref "U2") (pin "34") (pinfunction "P1[20]/MCFB0/PWM1[2]/SCK0_34") (pintype "passive"))
    )
    (net (code "107") (name "unconnected-(U2-P1[21]{slash}MCABORT{slash}PWM1[3]{slash}SSEL0-Pad35)") (class "Default")
      (node (ref "U2") (pin "35") (pinfunction "P1[21]/MCABORT/PWM1[3]/SSEL0_35") (pintype "passive"))
    )
    (net (code "108") (name "unconnected-(U2-P1[22]{slash}MC0B{slash}USB_PWRD{slash}MAT1[0]-Pad36)") (class "Default")
      (node (ref "U2") (pin "36") (pinfunction "P1[22]/MC0B/USB_PWRD/MAT1[0]_36") (pintype "passive"))
    )
    (net (code "109") (name "unconnected-(U2-P1[23]{slash}MCFB1{slash}PWM1[4]{slash}MISO0-Pad37)") (class "Default")
      (node (ref "U2") (pin "37") (pinfunction "P1[23]/MCFB1/PWM1[4]/MISO0_37") (pintype "passive"))
    )
    (net (code "110") (name "unconnected-(U2-P1[24]{slash}MCFB2{slash}PWM1[5]{slash}MOSI0-Pad38)") (class "Default")
      (node (ref "U2") (pin "38") (pinfunction "P1[24]/MCFB2/PWM1[5]/MOSI0_38") (pintype "passive"))
    )
    (net (code "111") (name "unconnected-(U2-P1[25]{slash}MC1A{slash}MAT1[1]-Pad39)") (class "Default")
      (node (ref "U2") (pin "39") (pinfunction "P1[25]/MC1A/MAT1[1]_39") (pintype "passive"))
    )
    (net (code "112") (name "unconnected-(U2-P1[26]{slash}MC1B{slash}PWM1[6]{slash}CAP0[0]-Pad40)") (class "Default")
      (node (ref "U2") (pin "40") (pinfunction "P1[26]/MC1B/PWM1[6]/CAP0[0]_40") (pintype "passive"))
    )
    (net (code "113") (name "unconnected-(U2-P1[27]{slash}CLKOUT{slash}~{USB_OVRCR}{slash}CAP0[1]-Pad43)") (class "Default")
      (node (ref "U2") (pin "43") (pinfunction "P1[27]/CLKOUT/~{USB_OVRCR}/CAP0[1]_43") (pintype "passive"))
    )
    (net (code "114") (name "unconnected-(U2-P1[28]{slash}MC2A{slash}PCAP1[0]{slash}MAT0[0]-Pad44)") (class "Default")
      (node (ref "U2") (pin "44") (pinfunction "P1[28]/MC2A/PCAP1[0]/MAT0[0]_44") (pintype "passive"))
    )
    (net (code "115") (name "unconnected-(U2-P1[29]{slash}MC2B{slash}PCAP1[1]{slash}MAT0[1]-Pad45)") (class "Default")
      (node (ref "U2") (pin "45") (pinfunction "P1[29]/MC2B/PCAP1[1]/MAT0[1]_45") (pintype "passive"))
    )
    (net (code "116") (name "unconnected-(U2-P1[31]{slash}SCK1{slash}AD0[5]-Pad20)") (class "Default")
      (node (ref "U2") (pin "20") (pinfunction "P1[31]/SCK1/AD0[5]_20") (pintype "passive"))
    )
    (net (code "117") (name "unconnected-(U2-P2[2]{slash}PWM1[3]{slash}CTS1{slash}TRACEDATA[3]-Pad73)") (class "Default")
      (node (ref "U2") (pin "73") (pinfunction "P2[2]/PWM1[3]/CTS1/TRACEDATA[3]_73") (pintype "passive+no_connect"))
    )
    (net (code "118") (name "unconnected-(U2-P2[3]{slash}PWM1[4]{slash}DCD1{slash}TRACEDATA[2]-Pad70)") (class "Default")
      (node (ref "U2") (pin "70") (pinfunction "P2[3]/PWM1[4]/DCD1/TRACEDATA[2]_70") (pintype "passive+no_connect"))
    )
    (net (code "119") (name "unconnected-(U2-P2[4]{slash}PWM1[5]{slash}DSR1{slash}TRACEDATA[1]-Pad69)") (class "Default")
      (node (ref "U2") (pin "69") (pinfunction "P2[4]/PWM1[5]/DSR1/TRACEDATA[1]_69") (pintype "passive"))
    )
    (net (code "120") (name "unconnected-(U2-P2[6]{slash}PCAP1[0]{slash}RI1{slash}TRACECLK-Pad67)") (class "Default")
      (node (ref "U2") (pin "67") (pinfunction "P2[6]/PCAP1[0]/RI1/TRACECLK_67") (pintype "passive+no_connect"))
    )
    (net (code "121") (name "unconnected-(U2-P2[7]{slash}RD2{slash}RTS1-Pad66)") (class "Default")
      (node (ref "U2") (pin "66") (pinfunction "P2[7]/RD2/RTS1_66") (pintype "passive+no_connect"))
    )
    (net (code "122") (name "unconnected-(U2-P2[8]{slash}TD2{slash}TXD2-Pad65)") (class "Default")
      (node (ref "U2") (pin "65") (pinfunction "P2[8]/TD2/TXD2_65") (pintype "passive+no_connect"))
    )
    (net (code "123") (name "unconnected-(U2-P4[28]{slash}RX_MCLK{slash}MAT2[0]{slash}TXD3-Pad82)") (class "Default")
      (node (ref "U2") (pin "82") (pinfunction "P4[28]/RX_MCLK/MAT2[0]/TXD3_82") (pintype "passive"))
    )
    (net (code "124") (name "unconnected-(U2-P4[29]{slash}TX_MCLK{slash}MAT2[1]{slash}RXD3-Pad85)") (class "Default")
      (node (ref "U2") (pin "85") (pinfunction "P4[29]/TX_MCLK/MAT2[1]/RXD3_85") (pintype "passive"))
    )
    (net (code "125") (name "unconnected-(U2-RTCK-Pad100)") (class "Default")
      (node (ref "U2") (pin "100") (pinfunction "RTCK_100") (pintype "passive"))
    )
    (net (code "126") (name "unconnected-(U2-TDI-Pad2)") (class "Default")
      (node (ref "U2") (pin "2") (pinfunction "TDI_2") (pintype "passive+no_connect"))
    )
    (net (code "127") (name "unconnected-(U2-TDO{slash}SWO-Pad1)") (class "Default")
      (node (ref "U2") (pin "1") (pinfunction "TDO/SWO_1") (pintype "passive+no_connect"))
    )
    (net (code "128") (name "unconnected-(U2-VBAT-Pad19)") (class "Default")
      (node (ref "U2") (pin "19") (pinfunction "VBAT_19") (pintype "passive"))
    )
    (net (code "129") (name "unconnected-(U2-VREF+-Pad12)") (class "Default")
      (node (ref "U2") (pin "12") (pinfunction "VREF+_12") (pintype "passive"))
    )
    (net (code "130") (name "unconnected-(U2-~{RSTOUT}-Pad14)") (class "Default")
      (node (ref "U2") (pin "14") (pinfunction "~{RSTOUT}_14") (pintype "passive"))
    )
    (net (code "131") (name "unconnected-(U2-~{TRST}-Pad4)") (class "Default")
      (node (ref "U2") (pin "4") (pinfunction "~{TRST}_4") (pintype "passive+no_connect"))
    )
    (net (code "132") (name "unconnected-(USB1-NC-Pad4)") (class "Default")
      (node (ref "USB1") (pin "4") (pinfunction "NC_4") (pintype "passive+no_connect"))
    )
  )
)
